# LEDs.net
KiCad netlist of a schematic drawn in Altium Designer
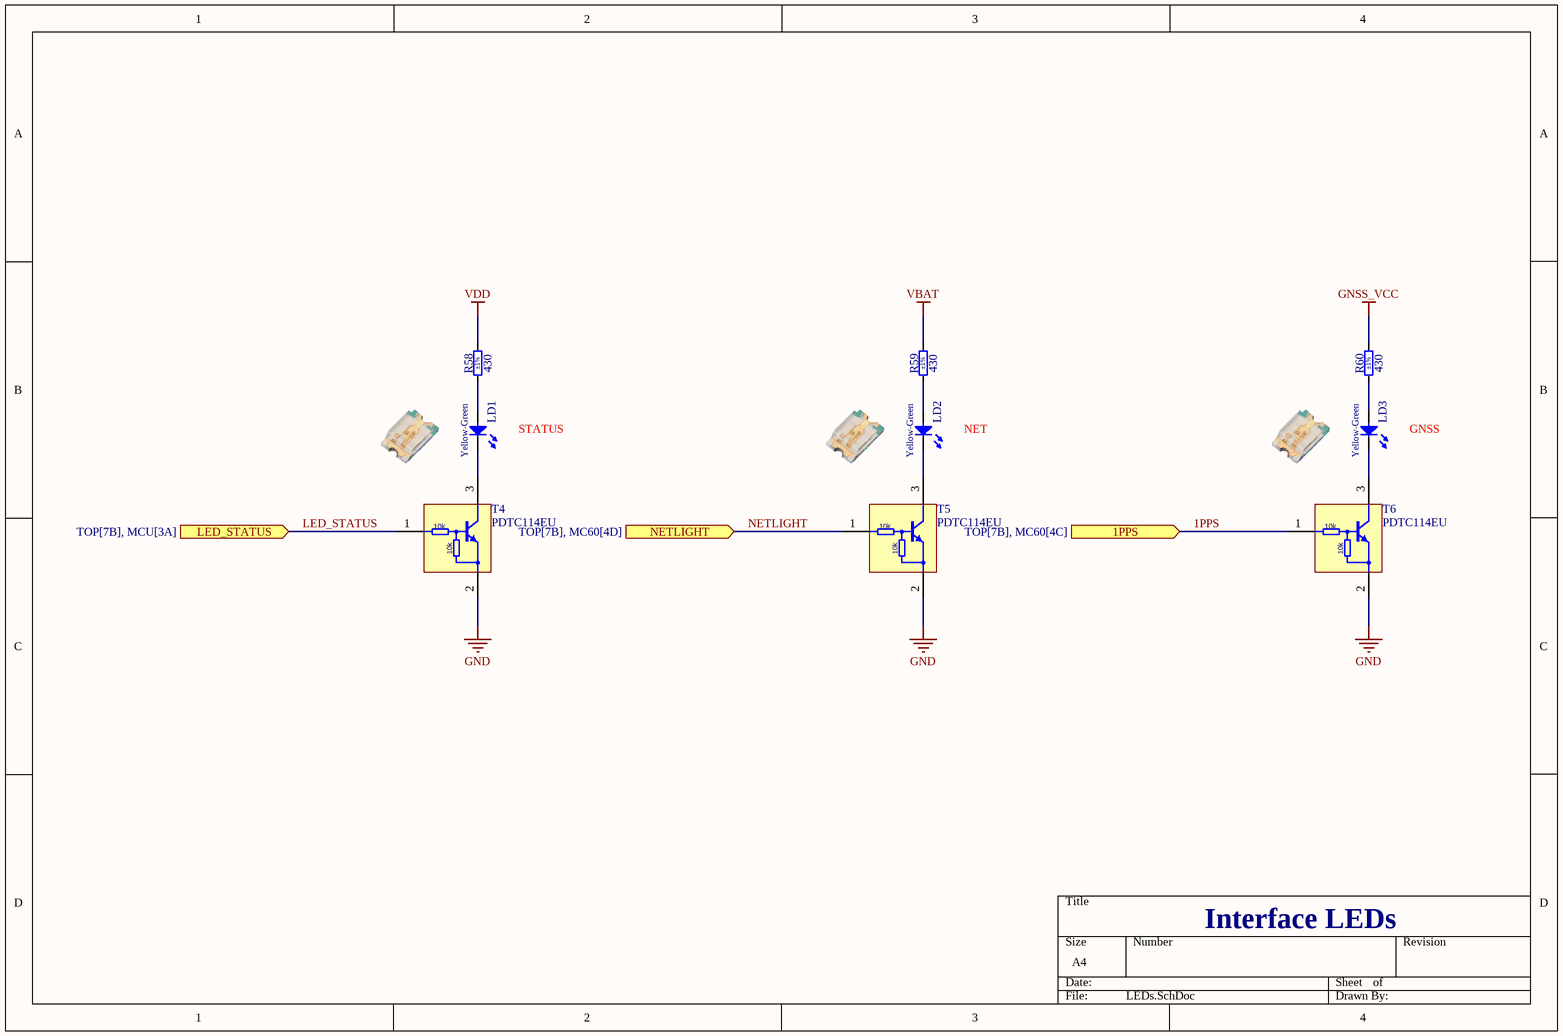
[diagram p0: LEDs.SchDoc]

(export (version "E")
  (design (tool "Eeschema 10.0.6"))
  (components
    (comp (ref "LD1")
      (value "Yellow-Green")
      (footprint "LED_DIALIGHT_598-8060-107F")
      (description "LED Yellow-Green 1C 2A")
      (fields
        (field (name "PART NUMBER") "LED_DIALIGHT_598-8060-107F")
        (field (name "MANUFACTURER") "DIALIGHT")
        (field (name "AUTHOR") "CERN DEM JLC")
      )
      (libsource (lib "ICs And Semiconductors") (part "LED Yellow Green 1C 2A"))
    )
    (comp (ref "LD2")
      (value "Yellow-Green")
      (footprint "LED_DIALIGHT_598-8060-107F")
      (description "LED Yellow-Green 1C 2A")
      (fields
        (field (name "PART NUMBER") "LED_DIALIGHT_598-8060-107F")
        (field (name "MANUFACTURER") "DIALIGHT")
        (field (name "AUTHOR") "CERN DEM JLC")
      )
      (libsource (lib "ICs And Semiconductors") (part "LED Yellow Green 1C 2A"))
    )
    (comp (ref "LD3")
      (value "Yellow-Green")
      (footprint "LED_DIALIGHT_598-8060-107F")
      (description "LED Yellow-Green 1C 2A")
      (fields
        (field (name "PART NUMBER") "LED_DIALIGHT_598-8060-107F")
        (field (name "MANUFACTURER") "DIALIGHT")
        (field (name "AUTHOR") "CERN DEM JLC")
      )
      (libsource (lib "ICs And Semiconductors") (part "LED Yellow Green 1C 2A"))
    )
    (comp (ref "R58")
      (value "430")
      (footprint "RESC1608X55N")
      (description "Resistor - 1%")
      (fields
        (field (name "TOLERANCE") "±1%")
        (field (name "PART NUMBER") "R0603_430R_1%_0.1W_100PPM")
        (field (name "POWER") "0.1W")
        (field (name "AUTHOR") "CERN DEM JLC")
      )
      (libsource (lib "Resistors") (part "Resistor - 1%"))
    )
    (comp (ref "R59")
      (value "430")
      (footprint "RESC1608X55N")
      (description "Resistor - 1%")
      (fields
        (field (name "TOLERANCE") "±1%")
        (field (name "PART NUMBER") "R0603_430R_1%_0.1W_100PPM")
        (field (name "POWER") "0.1W")
        (field (name "AUTHOR") "CERN DEM JLC")
      )
      (libsource (lib "Resistors") (part "Resistor - 1%"))
    )
    (comp (ref "R60")
      (value "430")
      (footprint "RESC1608X55N")
      (description "Resistor - 1%")
      (fields
        (field (name "TOLERANCE") "±1%")
        (field (name "PART NUMBER") "R0603_430R_1%_0.1W_100PPM")
        (field (name "POWER") "0.1W")
        (field (name "AUTHOR") "CERN DEM JLC")
      )
      (libsource (lib "Resistors") (part "Resistor - 1%"))
    )
    (comp (ref "T4")
      (value "PDTC114EU")
      (footprint "SOT65P210X100-3N")
      (description "Pre-Biased Bipolar Transistor (BJT) NPN - Pre-Biased 50 V 100 mA 200 mW Surface Mount SOT-323")
      (fields (field (name "MANUFACTURER") "Nexperia USA Inc.") (field (name "AUTHOR") "Xusniyor"))
      (libsource (lib "ICs And Semiconductors") (part "PDTC114EU"))
    )
    (comp (ref "T5")
      (value "PDTC114EU")
      (footprint "SOT65P210X100-3N")
      (description "Pre-Biased Bipolar Transistor (BJT) NPN - Pre-Biased 50 V 100 mA 200 mW Surface Mount SOT-323")
      (fields (field (name "MANUFACTURER") "Nexperia USA Inc.") (field (name "AUTHOR") "Xusniyor"))
      (libsource (lib "ICs And Semiconductors") (part "PDTC114EU"))
    )
    (comp (ref "T6")
      (value "PDTC114EU")
      (footprint "SOT65P210X100-3N")
      (description "Pre-Biased Bipolar Transistor (BJT) NPN - Pre-Biased 50 V 100 mA 200 mW Surface Mount SOT-323")
      (fields (field (name "MANUFACTURER") "Nexperia USA Inc.") (field (name "AUTHOR") "Xusniyor"))
      (libsource (lib "ICs And Semiconductors") (part "PDTC114EU"))
    )
  )
  (nets
    (net (code "1") (name "/1PPS") (class "Default")
      (node (ref "T6") (pin "1") (pinfunction "B_1") (pintype "passive"))
    )
    (net (code "2") (name "/LED_STATUS") (class "Default")
      (node (ref "T4") (pin "1") (pinfunction "B_1") (pintype "passive"))
    )
    (net (code "3") (name "/NETLIGHT") (class "Default")
      (node (ref "T5") (pin "1") (pinfunction "B_1") (pintype "passive"))
    )
    (net (code "4") (name "GND") (class "Default")
      (node (ref "T4") (pin "2") (pinfunction "E_2") (pintype "passive"))
      (node (ref "T5") (pin "2") (pinfunction "E_2") (pintype "passive"))
      (node (ref "T6") (pin "2") (pinfunction "E_2") (pintype "passive"))
    )
    (net (code "5") (name "GNSS_VCC") (class "Default")
      (node (ref "R60") (pin "2") (pinfunction "2_2") (pintype "passive"))
    )
    (net (code "6") (name "Net-(LD1-A)") (class "Default")
      (node (ref "LD1") (pin "2") (pinfunction "A_2") (pintype "passive"))
      (node (ref "R58") (pin "1") (pinfunction "1_1") (pintype "passive"))
    )
    (net (code "7") (name "Net-(LD1-C)") (class "Default")
      (node (ref "LD1") (pin "1") (pinfunction "C_1") (pintype "passive"))
      (node (ref "T4") (pin "3") (pinfunction "C_3") (pintype "passive"))
    )
    (net (code "8") (name "Net-(LD2-A)") (class "Default")
      (node (ref "LD2") (pin "2") (pinfunction "A_2") (pintype "passive"))
      (node (ref "R59") (pin "1") (pinfunction "1_1") (pintype "passive"))
    )
    (net (code "9") (name "Net-(LD2-C)") (class "Default")
      (node (ref "LD2") (pin "1") (pinfunction "C_1") (pintype "passive"))
      (node (ref "T5") (pin "3") (pinfunction "C_3") (pintype "passive"))
    )
    (net (code "10") (name "Net-(LD3-A)") (class "Default")
      (node (ref "LD3") (pin "2") (pinfunction "A_2") (pintype "passive"))
      (node (ref "R60") (pin "1") (pinfunction "1_1") (pintype "passive"))
    )
    (net (code "11") (name "Net-(LD3-C)") (class "Default")
      (node (ref "LD3") (pin "1") (pinfunction "C_1") (pintype "passive"))
      (node (ref "T6") (pin "3") (pinfunction "C_3") (pintype "passive"))
    )
    (net (code "12") (name "VBAT") (class "Default")
      (node (ref "R59") (pin "2") (pinfunction "2_2") (pintype "passive"))
    )
    (net (code "13") (name "VDD") (class "Default")
      (node (ref "R58") (pin "2") (pinfunction "2_2") (pintype "passive"))
    )
  )
)
